# Grove-Base-for-RasPi.net
KiCad netlist of a schematic drawn in EAGLE
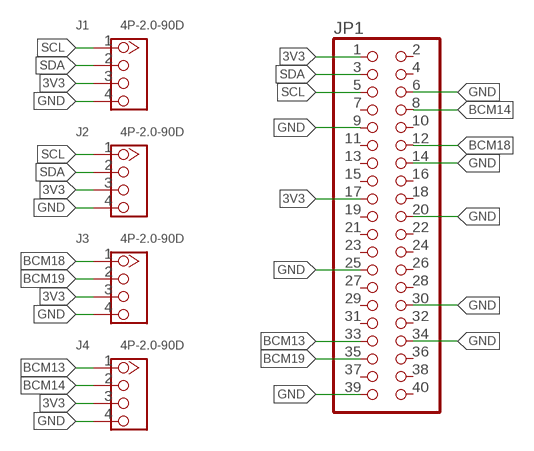
[diagram p0: schematic, sheet 1]

(export (version "E")
  (design (tool "Eeschema 10.0.6"))
  (components
    (comp (ref "J1")
      (value "4P-2.0-90D")
      (footprint "eagle-import:HW4-2.0-90D")
      (libsource (lib "eagle-import") (part "GROVE-CONNECTOR-DIP-90D(4P-2.0)"))
    )
    (comp (ref "J2")
      (value "4P-2.0-90D")
      (footprint "eagle-import:HW4-2.0-90D")
      (libsource (lib "eagle-import") (part "GROVE-CONNECTOR-DIP-90D(4P-2.0)"))
    )
    (comp (ref "J3")
      (value "4P-2.0-90D")
      (footprint "eagle-import:HW4-2.0-90D")
      (libsource (lib "eagle-import") (part "GROVE-CONNECTOR-DIP-90D(4P-2.0)"))
    )
    (comp (ref "J4")
      (value "4P-2.0-90D")
      (footprint "eagle-import:HW4-2.0-90D")
      (libsource (lib "eagle-import") (part "GROVE-CONNECTOR-DIP-90D(4P-2.0)"))
    )
    (comp (ref "JP1")
      (value "PINHD-2X20")
      (footprint "eagle-import:2X20")
      (libsource (lib "eagle-import") (part "PINHD-2X20"))
    )
  )
  (nets
    (net (code "1") (name "3V3") (class "Default")
      (node (ref "J1") (pin "3") (pinfunction "3_3") (pintype "bidirectional"))
      (node (ref "J2") (pin "3") (pinfunction "3_3") (pintype "bidirectional"))
      (node (ref "J3") (pin "3") (pinfunction "3_3") (pintype "bidirectional"))
      (node (ref "J4") (pin "3") (pinfunction "3_3") (pintype "bidirectional"))
      (node (ref "JP1") (pin "1") (pinfunction "1_1") (pintype "passive"))
      (node (ref "JP1") (pin "17") (pinfunction "17_17") (pintype "passive"))
    )
    (net (code "2") (name "BCM13") (class "Default")
      (node (ref "J4") (pin "1") (pinfunction "1_1") (pintype "bidirectional"))
      (node (ref "JP1") (pin "33") (pinfunction "33_33") (pintype "passive"))
    )
    (net (code "3") (name "BCM14") (class "Default")
      (node (ref "J4") (pin "2") (pinfunction "2_2") (pintype "bidirectional"))
      (node (ref "JP1") (pin "8") (pinfunction "8_8") (pintype "passive"))
    )
    (net (code "4") (name "BCM18") (class "Default")
      (node (ref "J3") (pin "1") (pinfunction "1_1") (pintype "bidirectional"))
      (node (ref "JP1") (pin "12") (pinfunction "12_12") (pintype "passive"))
    )
    (net (code "5") (name "BCM19") (class "Default")
      (node (ref "J3") (pin "2") (pinfunction "2_2") (pintype "bidirectional"))
      (node (ref "JP1") (pin "35") (pinfunction "35_35") (pintype "passive"))
    )
    (net (code "6") (name "GND") (class "Default")
      (node (ref "J1") (pin "4") (pinfunction "4_4") (pintype "bidirectional"))
      (node (ref "J2") (pin "4") (pinfunction "4_4") (pintype "bidirectional"))
      (node (ref "J3") (pin "4") (pinfunction "4_4") (pintype "bidirectional"))
      (node (ref "J4") (pin "4") (pinfunction "4_4") (pintype "bidirectional"))
      (node (ref "JP1") (pin "14") (pinfunction "14_14") (pintype "passive"))
      (node (ref "JP1") (pin "20") (pinfunction "20_20") (pintype "passive"))
      (node (ref "JP1") (pin "25") (pinfunction "25_25") (pintype "passive"))
      (node (ref "JP1") (pin "30") (pinfunction "30_30") (pintype "passive"))
      (node (ref "JP1") (pin "34") (pinfunction "34_34") (pintype "passive"))
      (node (ref "JP1") (pin "39") (pinfunction "39_39") (pintype "passive"))
      (node (ref "JP1") (pin "6") (pinfunction "6_6") (pintype "passive"))
      (node (ref "JP1") (pin "9") (pinfunction "9_9") (pintype "passive"))
    )
    (net (code "7") (name "SCL") (class "Default")
      (node (ref "J1") (pin "1") (pinfunction "1_1") (pintype "bidirectional"))
      (node (ref "J2") (pin "1") (pinfunction "1_1") (pintype "bidirectional"))
      (node (ref "JP1") (pin "5") (pinfunction "5_5") (pintype "passive"))
    )
    (net (code "8") (name "SDA") (class "Default")
      (node (ref "J1") (pin "2") (pinfunction "2_2") (pintype "bidirectional"))
      (node (ref "J2") (pin "2") (pinfunction "2_2") (pintype "bidirectional"))
      (node (ref "JP1") (pin "3") (pinfunction "3_3") (pintype "passive"))
    )
    (net (code "9") (name "unconnected-(JP1-Pad2)") (class "Default")
      (node (ref "JP1") (pin "2") (pinfunction "2_2") (pintype "passive"))
    )
    (net (code "10") (name "unconnected-(JP1-Pad4)") (class "Default")
      (node (ref "JP1") (pin "4") (pinfunction "4_4") (pintype "passive"))
    )
    (net (code "11") (name "unconnected-(JP1-Pad7)") (class "Default")
      (node (ref "JP1") (pin "7") (pinfunction "7_7") (pintype "passive"))
    )
    (net (code "12") (name "unconnected-(JP1-Pad10)") (class "Default")
      (node (ref "JP1") (pin "10") (pinfunction "10_10") (pintype "passive"))
    )
    (net (code "13") (name "unconnected-(JP1-Pad11)") (class "Default")
      (node (ref "JP1") (pin "11") (pinfunction "11_11") (pintype "passive"))
    )
    (net (code "14") (name "unconnected-(JP1-Pad13)") (class "Default")
      (node (ref "JP1") (pin "13") (pinfunction "13_13") (pintype "passive"))
    )
    (net (code "15") (name "unconnected-(JP1-Pad15)") (class "Default")
      (node (ref "JP1") (pin "15") (pinfunction "15_15") (pintype "passive"))
    )
    (net (code "16") (name "unconnected-(JP1-Pad16)") (class "Default")
      (node (ref "JP1") (pin "16") (pinfunction "16_16") (pintype "passive"))
    )
    (net (code "17") (name "unconnected-(JP1-Pad18)") (class "Default")
      (node (ref "JP1") (pin "18") (pinfunction "18_18") (pintype "passive"))
    )
    (net (code "18") (name "unconnected-(JP1-Pad19)") (class "Default")
      (node (ref "JP1") (pin "19") (pinfunction "19_19") (pintype "passive"))
    )
    (net (code "19") (name "unconnected-(JP1-Pad21)") (class "Default")
      (node (ref "JP1") (pin "21") (pinfunction "21_21") (pintype "passive"))
    )
    (net (code "20") (name "unconnected-(JP1-Pad22)") (class "Default")
      (node (ref "JP1") (pin "22") (pinfunction "22_22") (pintype "passive"))
    )
    (net (code "21") (name "unconnected-(JP1-Pad23)") (class "Default")
      (node (ref "JP1") (pin "23") (pinfunction "23_23") (pintype "passive"))
    )
    (net (code "22") (name "unconnected-(JP1-Pad24)") (class "Default")
      (node (ref "JP1") (pin "24") (pinfunction "24_24") (pintype "passive"))
    )
    (net (code "23") (name "unconnected-(JP1-Pad26)") (class "Default")
      (node (ref "JP1") (pin "26") (pinfunction "26_26") (pintype "passive"))
    )
    (net (code "24") (name "unconnected-(JP1-Pad27)") (class "Default")
      (node (ref "JP1") (pin "27") (pinfunction "27_27") (pintype "passive"))
    )
    (net (code "25") (name "unconnected-(JP1-Pad28)") (class "Default")
      (node (ref "JP1") (pin "28") (pinfunction "28_28") (pintype "passive"))
    )
    (net (code "26") (name "unconnected-(JP1-Pad29)") (class "Default")
      (node (ref "JP1") (pin "29") (pinfunction "29_29") (pintype "passive"))
    )
    (net (code "27") (name "unconnected-(JP1-Pad31)") (class "Default")
      (node (ref "JP1") (pin "31") (pinfunction "31_31") (pintype "passive"))
    )
    (net (code "28") (name "unconnected-(JP1-Pad32)") (class "Default")
      (node (ref "JP1") (pin "32") (pinfunction "32_32") (pintype "passive"))
    )
    (net (code "29") (name "unconnected-(JP1-Pad36)") (class "Default")
      (node (ref "JP1") (pin "36") (pinfunction "36_36") (pintype "passive"))
    )
    (net (code "30") (name "unconnected-(JP1-Pad37)") (class "Default")
      (node (ref "JP1") (pin "37") (pinfunction "37_37") (pintype "passive"))
    )
    (net (code "31") (name "unconnected-(JP1-Pad38)") (class "Default")
      (node (ref "JP1") (pin "38") (pinfunction "38_38") (pintype "passive"))
    )
    (net (code "32") (name "unconnected-(JP1-Pad40)") (class "Default")
      (node (ref "JP1") (pin "40") (pinfunction "40_40") (pintype "passive"))
    )
  )
)
